# Faulhaber_w_CPU_switchoutput.net
KiCad netlist of a schematic drawn in EAGLE
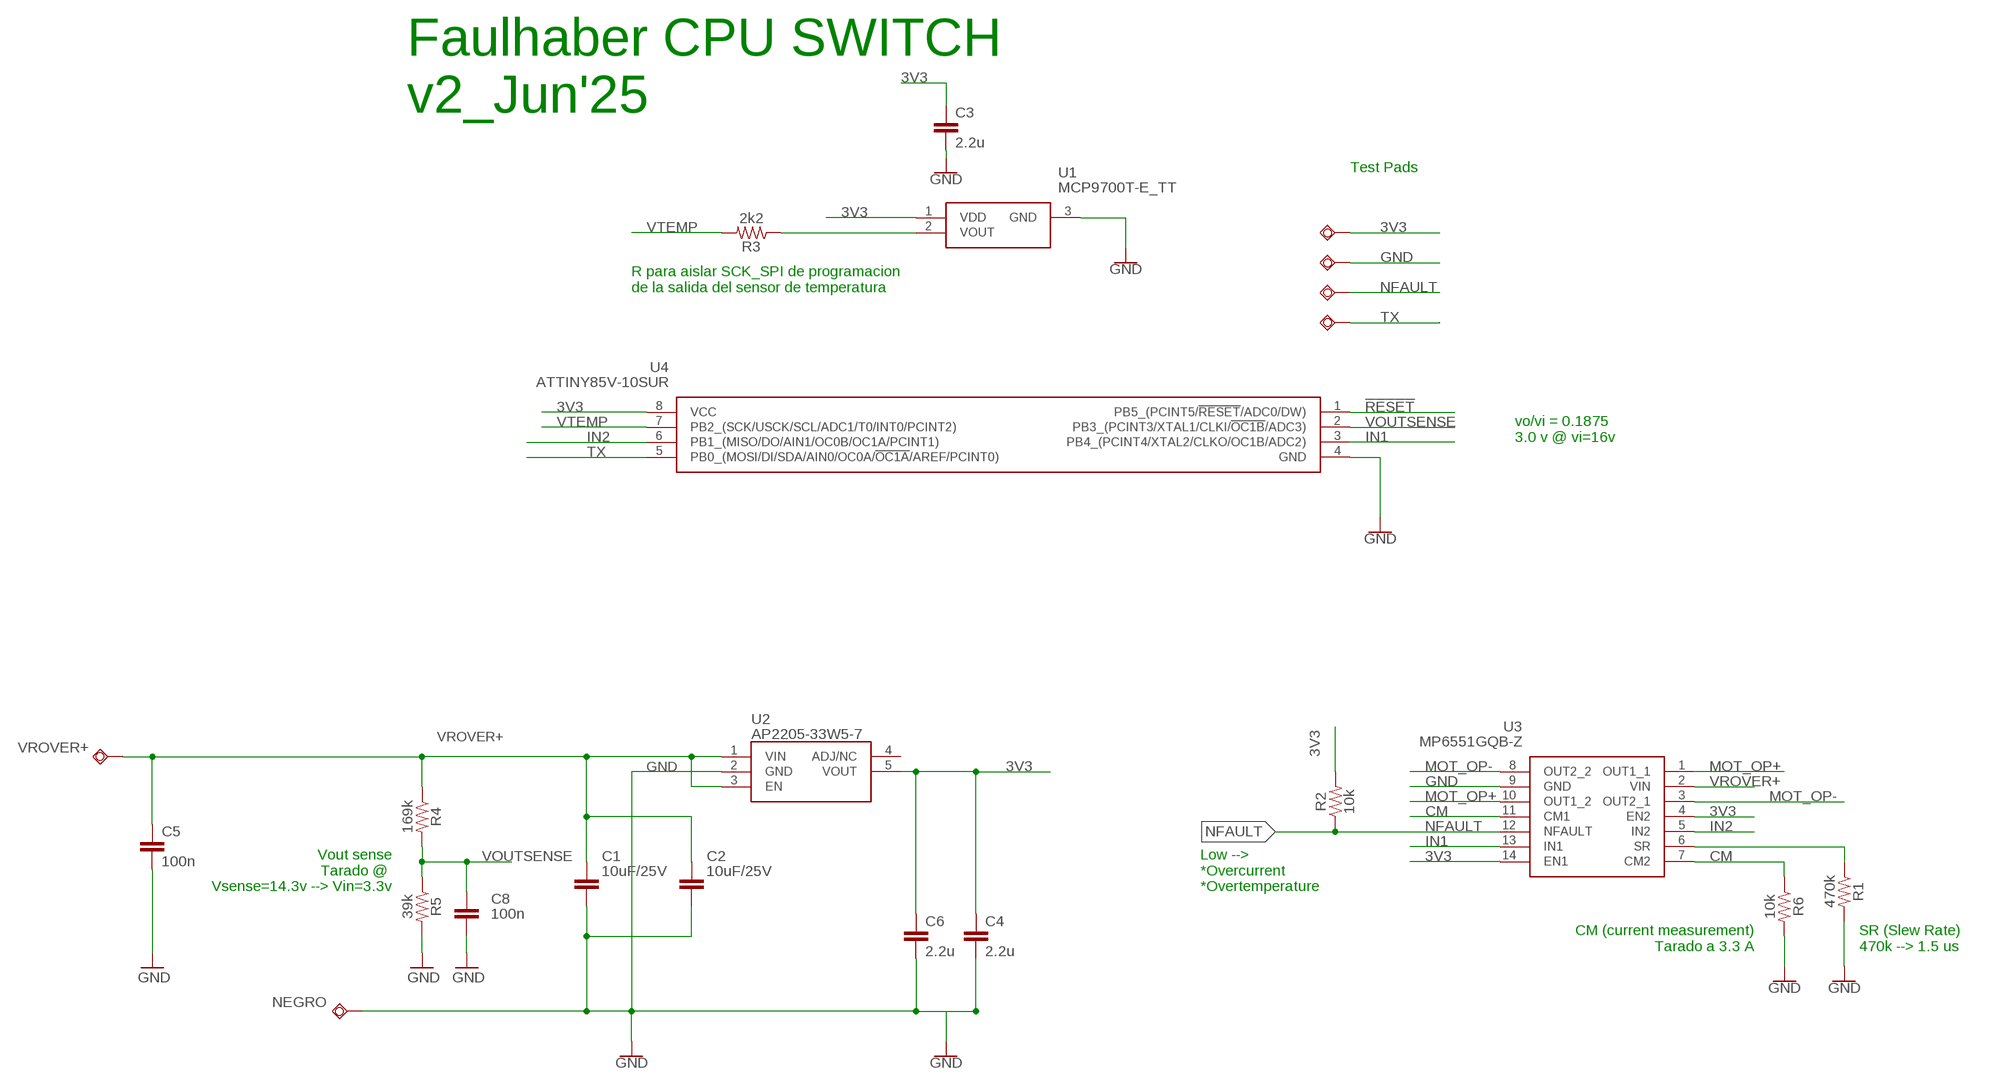
[diagram p0: schematic, sheet 1]

(export (version "E")
  (design (tool "Eeschema 10.0.6"))
  (components
    (comp (ref "3V3")
      (value "TESTPAD_TPSQB1,27")
      (footprint "eagle-import:TESTPAD_B1,27")
      (libsource (lib "eagle-import") (part "TESTPAD_TPSQB1,27"))
    )
    (comp (ref "C1")
      (value "10uF/25V")
      (footprint "eagle-import:CAPC2012X110")
      (libsource (lib "eagle-import") (part "CCHIP-0805(2012-METRIC)_"))
    )
    (comp (ref "C2")
      (value "10uF/25V")
      (footprint "eagle-import:CAPC2012X110")
      (libsource (lib "eagle-import") (part "CCHIP-0805(2012-METRIC)_"))
    )
    (comp (ref "C3")
      (value "2.2u")
      (footprint "eagle-import:0603-CAP")
      (libsource (lib "eagle-import") (part "4.7UF-6.3V-10%(0603)0603"))
    )
    (comp (ref "C4")
      (value "2.2u")
      (footprint "eagle-import:0603-CAP")
      (libsource (lib "eagle-import") (part "4.7UF-6.3V-10%(0603)0603"))
    )
    (comp (ref "C5")
      (value "100n")
      (footprint "eagle-import:0603-CAP")
      (libsource (lib "eagle-import") (part "4.7UF-6.3V-10%(0603)0603"))
    )
    (comp (ref "C6")
      (value "2.2u")
      (footprint "eagle-import:0603-CAP")
      (libsource (lib "eagle-import") (part "4.7UF-6.3V-10%(0603)0603"))
    )
    (comp (ref "C8")
      (value "100n")
      (footprint "eagle-import:0603")
      (libsource (lib "eagle-import") (part "0.1UF-0603-25V-(+80/-20%)"))
    )
    (comp (ref "GND")
      (value "TESTPAD_TPSQB1,27")
      (footprint "eagle-import:TESTPAD_B1,27")
      (libsource (lib "eagle-import") (part "TESTPAD_TPSQB1,27"))
    )
    (comp (ref "NEGRO")
      (value "TESTPAD_TPSQTP10SQ")
      (footprint "eagle-import:TESTPAD_TP10SQ")
      (libsource (lib "eagle-import") (part "BeagleBone_Blue_R3_5828899_TESTPAD_TPSQTP10SQ"))
    )
    (comp (ref "R1")
      (value "470k")
      (footprint "eagle-import:0603")
      (libsource (lib "eagle-import") (part "RESISTOR0603"))
    )
    (comp (ref "R2")
      (value "10k")
      (footprint "eagle-import:0603")
      (libsource (lib "eagle-import") (part "RESISTOR0603"))
    )
    (comp (ref "R3")
      (value "2k2")
      (footprint "eagle-import:0603")
      (libsource (lib "eagle-import") (part "RESISTOR0603"))
    )
    (comp (ref "R4")
      (value "169k")
      (footprint "eagle-import:0603")
      (libsource (lib "eagle-import") (part "RESISTOR0603"))
    )
    (comp (ref "R5")
      (value "39k")
      (footprint "eagle-import:0603")
      (libsource (lib "eagle-import") (part "RESISTOR0603"))
    )
    (comp (ref "R6")
      (value "10k")
      (footprint "eagle-import:0603")
      (libsource (lib "eagle-import") (part "RESISTOR0603"))
    )
    (comp (ref "U1")
      (value "MCP9700T-E_TT")
      (footprint "eagle-import:SOT95P237X112-3N")
      (fields
        (field (name "ARROW_PART_NUMBER") "MCP9700T-E/TT")
        (field (name "MOUSER_PART_NUMBER") "579-MCP9700T-E/TT")
      )
      (libsource (lib "eagle-import") (part "MCP9700T-E_TT"))
    )
    (comp (ref "U2")
      (value "AP2205-33W5-7")
      (footprint "eagle-import:SOT95P282X145-5N")
      (fields
        (field (name "MANUFACTURER_PART_NUMBER") "AP2205-W5-7")
        (field (name "MOUSER_PART_NUMBER") "621-AP2205-W5-7")
      )
      (libsource (lib "eagle-import") (part "AP2205-W5-7"))
    )
    (comp (ref "U3")
      (value "MP6551GQB-Z")
      (footprint "eagle-import:MP6551GQBZ")
      (fields (field (name "MOUSER_PART_NUMBER") "946-MP6551GQB-Z"))
      (libsource (lib "eagle-import") (part "MP6551GQB-Z"))
    )
    (comp (ref "U4")
      (value "ATTINY85V-10SUR")
      (footprint "eagle-import:SOIC127P798X216-8N")
      (fields (field (name "FARNELL2_PART_NUMBER") "2851618RL"))
      (libsource (lib "eagle-import") (part "ATTINY85V-10SUR"))
    )
    (comp (ref "USB+")
      (value "TESTPAD_TPSQB1,27")
      (footprint "eagle-import:TESTPAD_B1,27")
      (libsource (lib "eagle-import") (part "TESTPAD_TPSQB1,27"))
    )
    (comp (ref "USB-")
      (value "TESTPAD_TPSQB1,27")
      (footprint "eagle-import:TESTPAD_B1,27")
      (libsource (lib "eagle-import") (part "TESTPAD_TPSQB1,27"))
    )
    (comp (ref "VROVER+")
      (value "TESTPAD_TPSQTP10SQ")
      (footprint "eagle-import:TESTPAD_TP10SQ")
      (libsource (lib "eagle-import") (part "BeagleBone_Blue_R3_5828899_TESTPAD_TPSQTP10SQ"))
    )
  )
  (nets
    (net (code "1") (name "/3V3") (class "Default")
      (node (ref "3V3") (pin "TP") (pinfunction "TP_TP") (pintype "input"))
      (node (ref "C3") (pin "1") (pinfunction "1_1") (pintype "passive"))
      (node (ref "C4") (pin "1") (pinfunction "1_1") (pintype "passive"))
      (node (ref "C6") (pin "1") (pinfunction "1_1") (pintype "passive"))
      (node (ref "R2") (pin "2") (pinfunction "2_2") (pintype "passive"))
      (node (ref "U1") (pin "1") (pinfunction "VDD_1") (pintype "bidirectional"))
      (node (ref "U2") (pin "5") (pinfunction "VOUT_5") (pintype "bidirectional"))
      (node (ref "U3") (pin "14") (pinfunction "EN1_14") (pintype "bidirectional"))
      (node (ref "U3") (pin "4") (pinfunction "EN2_4") (pintype "bidirectional"))
      (node (ref "U4") (pin "8") (pinfunction "VCC_8") (pintype "bidirectional"))
    )
    (net (code "2") (name "/CM") (class "Default")
      (node (ref "R6") (pin "1") (pinfunction "1_1") (pintype "passive"))
      (node (ref "U3") (pin "11") (pinfunction "CM1_11") (pintype "bidirectional"))
      (node (ref "U3") (pin "7") (pinfunction "CM2_7") (pintype "bidirectional"))
    )
    (net (code "3") (name "/IN1") (class "Default")
      (node (ref "U3") (pin "13") (pinfunction "IN1_13") (pintype "bidirectional"))
      (node (ref "U4") (pin "3") (pinfunction "PB4_(PCINT4/XTAL2/CLKO/OC1B/ADC2)_3") (pintype "bidirectional"))
    )
    (net (code "4") (name "/IN2") (class "Default")
      (node (ref "U3") (pin "5") (pinfunction "IN2_5") (pintype "bidirectional"))
      (node (ref "U4") (pin "6") (pinfunction "PB1_(MISO/DO/AIN1/OC0B/OC1A/PCINT1)_6") (pintype "bidirectional"))
    )
    (net (code "5") (name "/MOT_OP+") (class "Default")
      (node (ref "U3") (pin "1") (pinfunction "OUT1_1_1") (pintype "bidirectional"))
      (node (ref "U3") (pin "10") (pinfunction "OUT1_2_10") (pintype "bidirectional"))
    )
    (net (code "6") (name "/MOT_OP-") (class "Default")
      (node (ref "U3") (pin "3") (pinfunction "OUT2_1_3") (pintype "bidirectional"))
      (node (ref "U3") (pin "8") (pinfunction "OUT2_2_8") (pintype "bidirectional"))
    )
    (net (code "7") (name "/TX") (class "Default")
      (node (ref "U4") (pin "5") (pinfunction "PB0_(MOSI/DI/SDA/AIN0/OC0A/~{OC1A}/AREF/PCINT0)_5") (pintype "bidirectional"))
      (node (ref "USB-") (pin "TP") (pinfunction "TP_TP") (pintype "input"))
    )
    (net (code "8") (name "/VOUTSENSE") (class "Default")
      (node (ref "C8") (pin "1") (pinfunction "1_1") (pintype "passive"))
      (node (ref "R4") (pin "2") (pinfunction "2_2") (pintype "passive"))
      (node (ref "R5") (pin "1") (pinfunction "1_1") (pintype "passive"))
      (node (ref "U4") (pin "2") (pinfunction "PB3_(PCINT3/XTAL1/CLKI/~{OC1B}/ADC3)_2") (pintype "bidirectional"))
    )
    (net (code "9") (name "/VROVER+") (class "Default")
      (node (ref "C1") (pin "1") (pinfunction "1_1") (pintype "passive"))
      (node (ref "C2") (pin "1") (pinfunction "1_1") (pintype "passive"))
      (node (ref "C5") (pin "1") (pinfunction "1_1") (pintype "passive"))
      (node (ref "R4") (pin "1") (pinfunction "1_1") (pintype "passive"))
      (node (ref "U2") (pin "1") (pinfunction "VIN_1") (pintype "bidirectional"))
      (node (ref "U2") (pin "3") (pinfunction "EN_3") (pintype "bidirectional"))
      (node (ref "U3") (pin "2") (pinfunction "VIN_2") (pintype "bidirectional"))
      (node (ref "VROVER+") (pin "TP") (pinfunction "TP_TP") (pintype "input"))
    )
    (net (code "10") (name "/VTEMP") (class "Default")
      (node (ref "R3") (pin "2") (pinfunction "2_2") (pintype "passive"))
      (node (ref "U4") (pin "7") (pinfunction "PB2_(SCK/USCK/SCL/ADC1/T0/INT0/PCINT2)_7") (pintype "bidirectional"))
    )
    (net (code "11") (name "/~{RESET}") (class "Default")
      (node (ref "U4") (pin "1") (pinfunction "PB5_(PCINT5/~{RESET}/ADC0/DW)_1") (pintype "bidirectional"))
    )
    (net (code "12") (name "GND") (class "Default")
      (node (ref "C1") (pin "2") (pinfunction "2_2") (pintype "passive"))
      (node (ref "C2") (pin "2") (pinfunction "2_2") (pintype "passive"))
      (node (ref "C3") (pin "2") (pinfunction "2_2") (pintype "passive"))
      (node (ref "C4") (pin "2") (pinfunction "2_2") (pintype "passive"))
      (node (ref "C5") (pin "2") (pinfunction "2_2") (pintype "passive"))
      (node (ref "C6") (pin "2") (pinfunction "2_2") (pintype "passive"))
      (node (ref "C8") (pin "2") (pinfunction "2_2") (pintype "passive"))
      (node (ref "GND") (pin "TP") (pinfunction "TP_TP") (pintype "input"))
      (node (ref "NEGRO") (pin "TP") (pinfunction "TP_TP") (pintype "input"))
      (node (ref "R1") (pin "2") (pinfunction "2_2") (pintype "passive"))
      (node (ref "R5") (pin "2") (pinfunction "2_2") (pintype "passive"))
      (node (ref "R6") (pin "2") (pinfunction "2_2") (pintype "passive"))
      (node (ref "U1") (pin "3") (pinfunction "GND_3") (pintype "bidirectional"))
      (node (ref "U2") (pin "2") (pinfunction "GND_2") (pintype "bidirectional"))
      (node (ref "U3") (pin "9") (pinfunction "GND_9") (pintype "bidirectional"))
      (node (ref "U4") (pin "4") (pinfunction "GND_4") (pintype "bidirectional"))
    )
    (net (code "13") (name "NFAULT") (class "Default")
      (node (ref "R2") (pin "1") (pinfunction "1_1") (pintype "passive"))
      (node (ref "U3") (pin "12") (pinfunction "NFAULT_12") (pintype "bidirectional"))
      (node (ref "USB+") (pin "TP") (pinfunction "TP_TP") (pintype "input"))
    )
    (net (code "14") (name "Net-(U1-VOUT)") (class "Default")
      (node (ref "R3") (pin "1") (pinfunction "1_1") (pintype "passive"))
      (node (ref "U1") (pin "2") (pinfunction "VOUT_2") (pintype "bidirectional"))
    )
    (net (code "15") (name "Net-(U3-SR)") (class "Default")
      (node (ref "R1") (pin "1") (pinfunction "1_1") (pintype "passive"))
      (node (ref "U3") (pin "6") (pinfunction "SR_6") (pintype "bidirectional"))
    )
    (net (code "16") (name "unconnected-(U2-ADJ{slash}NC-Pad4)") (class "Default")
      (node (ref "U2") (pin "4") (pinfunction "ADJ/NC_4") (pintype "bidirectional"))
    )
  )
)
